# High_Current_Sense.net
KiCad netlist of a schematic drawn in Altium Designer
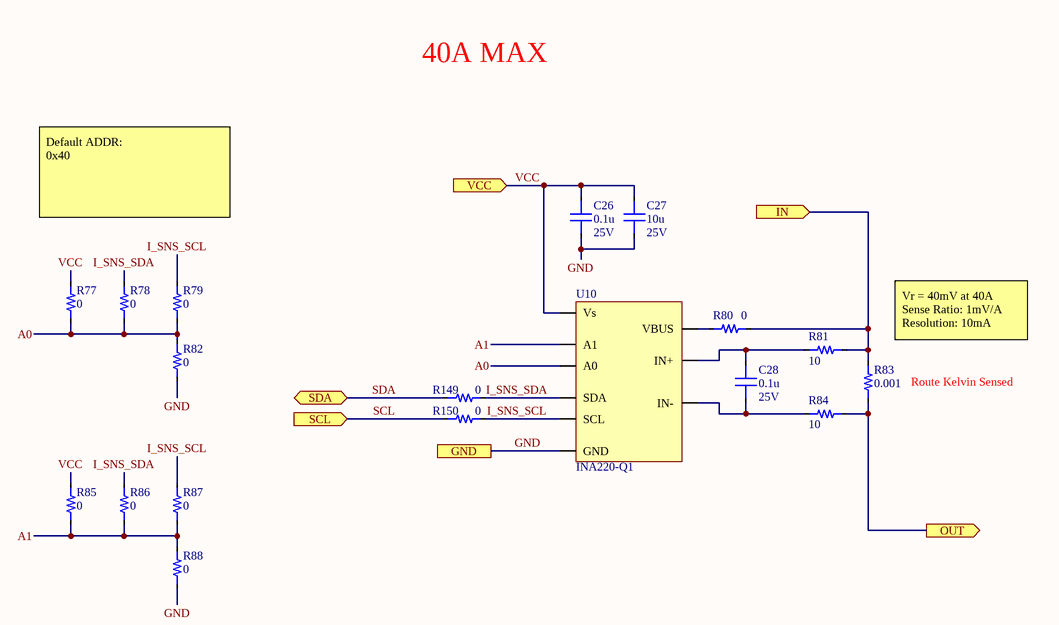
[diagram p0: High_Current_Sense.SchDoc]

(export (version "E")
  (design (tool "Eeschema 10.0.6"))
  (components
    (comp (ref "C26")
      (value "0.1u")
      (footprint "0603_CAP")
      (fields (field (name "VOLTAGE") "25V") (field (name "Comment") "Capacitor"))
      (libsource (lib "Capacitors") (part "Capacitor"))
    )
    (comp (ref "C27")
      (value "10u")
      (footprint "0805_CAP")
      (fields (field (name "VOLTAGE") "25V") (field (name "Comment") "Capacitor"))
      (libsource (lib "Capacitors") (part "Capacitor"))
    )
    (comp (ref "C28")
      (value "0.1u")
      (footprint "0603_CAP")
      (fields (field (name "VOLTAGE") "25V") (field (name "Comment") "Capacitor"))
      (libsource (lib "Capacitors") (part "Capacitor"))
    )
    (comp (ref "R77")
      (value "0")
      (footprint "0603_RES")
      (fields (field (name "Comment") "Resistor"))
      (libsource (lib "Resistors") (part "Resistor"))
    )
    (comp (ref "R78")
      (value "0")
      (footprint "0603_RES")
      (fields (field (name "Comment") "Resistor"))
      (libsource (lib "Resistors") (part "Resistor"))
    )
    (comp (ref "R79")
      (value "0")
      (footprint "0603_RES")
      (fields (field (name "Comment") "Resistor"))
      (libsource (lib "Resistors") (part "Resistor"))
    )
    (comp (ref "R80")
      (value "0")
      (footprint "0603_RES")
      (fields (field (name "Comment") "Resistor"))
      (libsource (lib "Resistors") (part "Resistor"))
    )
    (comp (ref "R81")
      (value "10")
      (footprint "0603_RES")
      (fields (field (name "Comment") "Resistor"))
      (libsource (lib "Resistors") (part "Resistor"))
    )
    (comp (ref "R82")
      (value "0")
      (footprint "0603_RES")
      (fields (field (name "Comment") "Resistor"))
      (libsource (lib "Resistors") (part "Resistor"))
    )
    (comp (ref "R83")
      (value "0.001")
      (footprint "2512_RES")
      (fields (field (name "TOLERANCE") "1%") (field (name "POWER") "2") (field (name "Comment") "Resistor"))
      (libsource (lib "Resistors") (part "Resistor"))
    )
    (comp (ref "R84")
      (value "10")
      (footprint "0603_RES")
      (fields (field (name "Comment") "Resistor"))
      (libsource (lib "Resistors") (part "Resistor"))
    )
    (comp (ref "R85")
      (value "0")
      (footprint "0603_RES")
      (fields (field (name "Comment") "Resistor"))
      (libsource (lib "Resistors") (part "Resistor"))
    )
    (comp (ref "R86")
      (value "0")
      (footprint "0603_RES")
      (fields (field (name "Comment") "Resistor"))
      (libsource (lib "Resistors") (part "Resistor"))
    )
    (comp (ref "R87")
      (value "0")
      (footprint "0603_RES")
      (fields (field (name "Comment") "Resistor"))
      (libsource (lib "Resistors") (part "Resistor"))
    )
    (comp (ref "R88")
      (value "0")
      (footprint "0603_RES")
      (fields (field (name "Comment") "Resistor"))
      (libsource (lib "Resistors") (part "Resistor"))
    )
    (comp (ref "R149")
      (value "0")
      (footprint "0603_RES")
      (fields (field (name "Comment") "Resistor"))
      (libsource (lib "Resistors") (part "Resistor"))
    )
    (comp (ref "R150")
      (value "0")
      (footprint "0603_RES")
      (fields (field (name "Comment") "Resistor"))
      (libsource (lib "Resistors") (part "Resistor"))
    )
    (comp (ref "U10")
      (value "INA220-Q1")
      (footprint "TSSOP-10")
      (description "Current Monitor Regulator High/Low-Side 10mA 10-VSSOP")
      (libsource (lib "Analog_IC") (part "INA220-Q1"))
    )
  )
  (nets
    (net (code "1") (name "/A0") (class "Default")
      (node (ref "R77") (pin "1") (pinfunction "1_1") (pintype "passive"))
      (node (ref "R78") (pin "1") (pinfunction "1_1") (pintype "passive"))
      (node (ref "R79") (pin "1") (pinfunction "1_1") (pintype "passive"))
      (node (ref "R82") (pin "2") (pinfunction "2_2") (pintype "passive"))
      (node (ref "U10") (pin "2") (pinfunction "A0_2") (pintype "passive"))
    )
    (net (code "2") (name "/A1") (class "Default")
      (node (ref "R85") (pin "1") (pinfunction "1_1") (pintype "passive"))
      (node (ref "R86") (pin "1") (pinfunction "1_1") (pintype "passive"))
      (node (ref "R87") (pin "1") (pinfunction "1_1") (pintype "passive"))
      (node (ref "R88") (pin "2") (pinfunction "2_2") (pintype "passive"))
      (node (ref "U10") (pin "1") (pinfunction "A1_1") (pintype "passive"))
    )
    (net (code "3") (name "/GND") (class "Default")
      (node (ref "C26") (pin "1") (pinfunction "1_1") (pintype "passive"))
      (node (ref "C27") (pin "1") (pinfunction "1_1") (pintype "passive"))
      (node (ref "R82") (pin "1") (pinfunction "1_1") (pintype "passive"))
      (node (ref "R88") (pin "1") (pinfunction "1_1") (pintype "passive"))
      (node (ref "U10") (pin "7") (pinfunction "GND_7") (pintype "passive"))
    )
    (net (code "4") (name "/IN") (class "Default")
      (node (ref "R80") (pin "2") (pinfunction "2_2") (pintype "passive"))
      (node (ref "R81") (pin "2") (pinfunction "2_2") (pintype "passive"))
      (node (ref "R83") (pin "2") (pinfunction "2_2") (pintype "passive"))
    )
    (net (code "5") (name "/I_SNS_SCL") (class "Default")
      (node (ref "R150") (pin "2") (pinfunction "2_2") (pintype "passive"))
      (node (ref "R79") (pin "2") (pinfunction "2_2") (pintype "passive"))
      (node (ref "R87") (pin "2") (pinfunction "2_2") (pintype "passive"))
      (node (ref "U10") (pin "5") (pinfunction "SCL_5") (pintype "passive"))
    )
    (net (code "6") (name "/I_SNS_SDA") (class "Default")
      (node (ref "R149") (pin "2") (pinfunction "2_2") (pintype "passive"))
      (node (ref "R78") (pin "2") (pinfunction "2_2") (pintype "passive"))
      (node (ref "R86") (pin "2") (pinfunction "2_2") (pintype "passive"))
      (node (ref "U10") (pin "4") (pinfunction "SDA_4") (pintype "passive"))
    )
    (net (code "7") (name "/OUT") (class "Default")
      (node (ref "R83") (pin "1") (pinfunction "1_1") (pintype "passive"))
      (node (ref "R84") (pin "2") (pinfunction "2_2") (pintype "passive"))
    )
    (net (code "8") (name "/SCL") (class "Default")
      (node (ref "R150") (pin "1") (pinfunction "1_1") (pintype "passive"))
    )
    (net (code "9") (name "/SDA") (class "Default")
      (node (ref "R149") (pin "1") (pinfunction "1_1") (pintype "passive"))
    )
    (net (code "10") (name "/VCC") (class "Default")
      (node (ref "C26") (pin "2") (pinfunction "2_2") (pintype "passive"))
      (node (ref "C27") (pin "2") (pinfunction "2_2") (pintype "passive"))
      (node (ref "R77") (pin "2") (pinfunction "2_2") (pintype "passive"))
      (node (ref "R85") (pin "2") (pinfunction "2_2") (pintype "passive"))
      (node (ref "U10") (pin "6") (pinfunction "Vs_6") (pintype "passive"))
    )
    (net (code "11") (name "Net-(U10-IN+)") (class "Default")
      (node (ref "C28") (pin "2") (pinfunction "2_2") (pintype "passive"))
      (node (ref "R81") (pin "1") (pinfunction "1_1") (pintype "passive"))
      (node (ref "U10") (pin "10") (pinfunction "IN+_10") (pintype "passive"))
    )
    (net (code "12") (name "Net-(U10-IN-)") (class "Default")
      (node (ref "C28") (pin "1") (pinfunction "1_1") (pintype "passive"))
      (node (ref "R84") (pin "1") (pinfunction "1_1") (pintype "passive"))
      (node (ref "U10") (pin "9") (pinfunction "IN-_9") (pintype "passive"))
    )
    (net (code "13") (name "Net-(U10-VBUS)") (class "Default")
      (node (ref "R80") (pin "1") (pinfunction "1_1") (pintype "passive"))
      (node (ref "U10") (pin "8") (pinfunction "VBUS_8") (pintype "passive"))
    )
  )
)
